# eagle_schematic.net
KiCad netlist of a schematic drawn in EAGLE
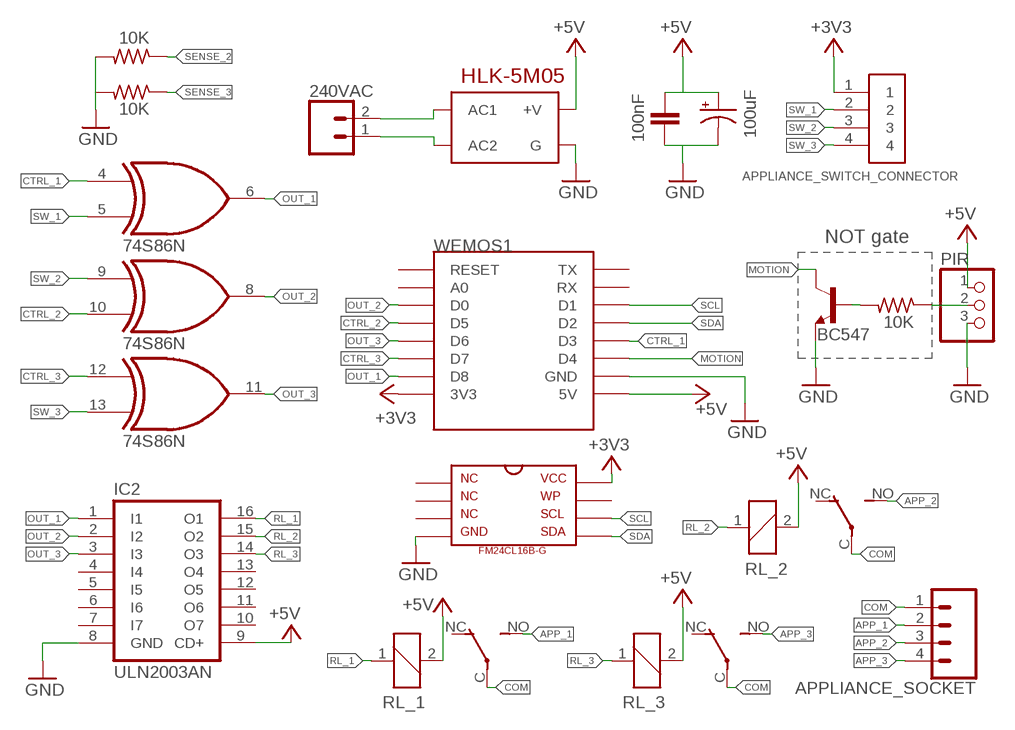
[diagram p0: schematic, sheet 1]

(export (version "E")
  (design (tool "Eeschema 10.0.6"))
  (components
    (comp (ref "240VAC")
      (value "CONN_025MM")
      (footprint "eagle-import:SCREWTERMINAL-5MM-2")
      (libsource (lib "eagle-import") (part "CONN_025MM"))
    )
    (comp (ref "APPLIANCE_SOCKET")
      (value "CONN_04SCREW_LOCK")
      (footprint "eagle-import:SCREWTERMINAL-3.5MM-4_LOCK")
      (libsource (lib "eagle-import") (part "CONN_04SCREW_LOCK"))
    )
    (comp (ref "APPLIANCE_SWITCH_CONNECTOR")
      (value "1X4-BIG")
      (footprint "eagle-import:1X04-BIG")
      (libsource (lib "eagle-import") (part "1X4-BIG"))
    )
    (comp (ref "C1")
      (value "100nF")
      (footprint "eagle-import:C5B2.5")
      (libsource (lib "eagle-import") (part "C5/2.5"))
    )
    (comp (ref "C2")
      (value "100uF")
      (footprint "eagle-import:B45181B")
      (libsource (lib "eagle-import") (part "CPOL-USB45181B"))
    )
    (comp (ref "IC1")
      (value "74S86N")
      (footprint "eagle-import:DIL14")
      (libsource (lib "eagle-import") (part "7486NS"))
    )
    (comp (ref "IC2")
      (value "ULN2003AN")
      (footprint "eagle-import:DIL16")
      (libsource (lib "eagle-import") (part "ULN2003AN"))
    )
    (comp (ref "PIR")
      (value "PINHD-1X3CB")
      (footprint "eagle-import:1X03-CLEANBIG")
      (libsource (lib "eagle-import") (part "PINHD-1X3CB"))
    )
    (comp (ref "R1")
      (value "10K")
      (footprint "eagle-import:0204_7")
      (libsource (lib "eagle-import") (part "R-US_0204/7"))
    )
    (comp (ref "R2")
      (value "10K")
      (footprint "eagle-import:0204_7")
      (libsource (lib "eagle-import") (part "R-US_0204/7"))
    )
    (comp (ref "R3")
      (value "10K")
      (footprint "eagle-import:0204_7")
      (libsource (lib "eagle-import") (part "R-US_0204/7"))
    )
    (comp (ref "RL_1")
      (value "CQ1-12V")
      (footprint "eagle-import:CQ1")
      (libsource (lib "eagle-import") (part "CQ1-12V"))
    )
    (comp (ref "RL_2")
      (value "CQ1-12V")
      (footprint "eagle-import:CQ1")
      (libsource (lib "eagle-import") (part "CQ1-12V"))
    )
    (comp (ref "RL_3")
      (value "CQ1-12V")
      (footprint "eagle-import:CQ1")
      (libsource (lib "eagle-import") (part "CQ1-12V"))
    )
    (comp (ref "T1")
      (value "BC547")
      (footprint "eagle-import:TO92")
      (libsource (lib "eagle-import") (part "BC547"))
    )
    (comp (ref "U$1")
      (value "HLK-5M05")
      (footprint "eagle-import:HLK-5M05")
      (libsource (lib "eagle-import") (part "HLK-5M05"))
    )
    (comp (ref "U$3")
      (value "FM24CL16B-G")
      (footprint "eagle-import:FM24CL16B-G")
      (libsource (lib "eagle-import") (part "FM24CL16B-G"))
    )
    (comp (ref "WEMOS1")
      (value "WEMOS-D1-MINI")
      (footprint "eagle-import:WEMOS-D1-MINI")
      (libsource (lib "eagle-import") (part "WEMOS-D1-MINI"))
    )
  )
  (nets
    (net (code "1") (name "+3V3") (class "Default")
      (node (ref "APPLIANCE_SWITCH_CONNECTOR") (pin "1") (pinfunction "1_1") (pintype "bidirectional"))
      (node (ref "U$3") (pin "8") (pinfunction "8_8") (pintype "power_in"))
      (node (ref "WEMOS1") (pin "3V3") (pinfunction "3V3_3V3") (pintype "bidirectional"))
    )
    (net (code "2") (name "+5V") (class "Default")
      (node (ref "C1") (pin "1") (pinfunction "1_1") (pintype "passive"))
      (node (ref "C2") (pin "+") (pinfunction "+_+") (pintype "passive"))
      (node (ref "IC2") (pin "9") (pinfunction "CD+_9") (pintype "passive"))
      (node (ref "PIR") (pin "1") (pinfunction "1_1") (pintype "passive"))
      (node (ref "RL_1") (pin "2") (pinfunction "2_2") (pintype "passive"))
      (node (ref "RL_2") (pin "2") (pinfunction "2_2") (pintype "passive"))
      (node (ref "RL_3") (pin "2") (pinfunction "2_2") (pintype "passive"))
      (node (ref "U$1") (pin "+V") (pinfunction "+V_+V") (pintype "bidirectional"))
      (node (ref "WEMOS1") (pin "5V") (pinfunction "5V_5V") (pintype "bidirectional"))
    )
    (net (code "3") (name "APP_1") (class "Default")
      (node (ref "APPLIANCE_SOCKET") (pin "2") (pinfunction "2_2") (pintype "passive"))
      (node (ref "RL_1") (pin "NO") (pinfunction "S_NO") (pintype "passive"))
    )
    (net (code "4") (name "APP_2") (class "Default")
      (node (ref "APPLIANCE_SOCKET") (pin "3") (pinfunction "3_3") (pintype "passive"))
      (node (ref "RL_2") (pin "NO") (pinfunction "S_NO") (pintype "passive"))
    )
    (net (code "5") (name "APP_3") (class "Default")
      (node (ref "APPLIANCE_SOCKET") (pin "4") (pinfunction "4_4") (pintype "passive"))
      (node (ref "RL_3") (pin "NO") (pinfunction "S_NO") (pintype "passive"))
    )
    (net (code "6") (name "COM") (class "Default")
      (node (ref "APPLIANCE_SOCKET") (pin "1") (pinfunction "1_1") (pintype "passive"))
      (node (ref "RL_1") (pin "C") (pinfunction "P_C") (pintype "passive"))
      (node (ref "RL_2") (pin "C") (pinfunction "P_C") (pintype "passive"))
      (node (ref "RL_3") (pin "C") (pinfunction "P_C") (pintype "passive"))
    )
    (net (code "7") (name "CTRL_1") (class "Default")
      (node (ref "IC1") (pin "4") (pinfunction "I0_4") (pintype "input"))
      (node (ref "WEMOS1") (pin "D3") (pinfunction "D3_D3") (pintype "bidirectional"))
    )
    (net (code "8") (name "CTRL_2") (class "Default")
      (node (ref "IC1") (pin "10") (pinfunction "I1_10") (pintype "input"))
      (node (ref "WEMOS1") (pin "D5") (pinfunction "D5_D5") (pintype "bidirectional"))
    )
    (net (code "9") (name "CTRL_3") (class "Default")
      (node (ref "IC1") (pin "12") (pinfunction "I0_12") (pintype "input"))
      (node (ref "WEMOS1") (pin "D7") (pinfunction "D7_D7") (pintype "bidirectional"))
    )
    (net (code "10") (name "GND") (class "Default")
      (node (ref "C1") (pin "2") (pinfunction "2_2") (pintype "passive"))
      (node (ref "C2") (pin "-") (pinfunction "-_-") (pintype "passive"))
      (node (ref "IC2") (pin "8") (pinfunction "GND_8") (pintype "power_in"))
      (node (ref "PIR") (pin "3") (pinfunction "3_3") (pintype "passive"))
      (node (ref "R2") (pin "2") (pinfunction "2_2") (pintype "passive"))
      (node (ref "R3") (pin "2") (pinfunction "2_2") (pintype "passive"))
      (node (ref "T1") (pin "1") (pinfunction "E_1") (pintype "passive"))
      (node (ref "U$1") (pin "G") (pinfunction "G_G") (pintype "bidirectional"))
      (node (ref "U$3") (pin "4") (pinfunction "4_4") (pintype "power_in"))
      (node (ref "WEMOS1") (pin "GND") (pinfunction "GND_GND") (pintype "bidirectional"))
    )
    (net (code "11") (name "MOTION") (class "Default")
      (node (ref "T1") (pin "3") (pinfunction "C_3") (pintype "passive"))
      (node (ref "WEMOS1") (pin "D4") (pinfunction "D4_D4") (pintype "bidirectional"))
    )
    (net (code "12") (name "Net-(240VAC-Pad1)") (class "Default")
      (node (ref "240VAC") (pin "1") (pinfunction "1_1") (pintype "passive"))
      (node (ref "U$1") (pin "AC2") (pinfunction "AC2_AC2") (pintype "bidirectional"))
    )
    (net (code "13") (name "Net-(240VAC-Pad2)") (class "Default")
      (node (ref "240VAC") (pin "2") (pinfunction "2_2") (pintype "passive"))
      (node (ref "U$1") (pin "AC1") (pinfunction "AC1_AC1") (pintype "bidirectional"))
    )
    (net (code "14") (name "Net-(PIR-Pad2)") (class "Default")
      (node (ref "PIR") (pin "2") (pinfunction "2_2") (pintype "passive"))
      (node (ref "R1") (pin "1") (pinfunction "1_1") (pintype "passive"))
    )
    (net (code "15") (name "Net-(T1-B)") (class "Default")
      (node (ref "R1") (pin "2") (pinfunction "2_2") (pintype "passive"))
      (node (ref "T1") (pin "2") (pinfunction "B_2") (pintype "passive"))
    )
    (net (code "16") (name "OUT_1") (class "Default")
      (node (ref "IC1") (pin "6") (pinfunction "O_6") (pintype "output"))
      (node (ref "IC2") (pin "1") (pinfunction "I1_1") (pintype "input"))
      (node (ref "WEMOS1") (pin "D8") (pinfunction "D8_D8") (pintype "bidirectional"))
    )
    (net (code "17") (name "OUT_2") (class "Default")
      (node (ref "IC1") (pin "8") (pinfunction "O_8") (pintype "output"))
      (node (ref "IC2") (pin "2") (pinfunction "I2_2") (pintype "input"))
      (node (ref "WEMOS1") (pin "D0") (pinfunction "D0_D0") (pintype "bidirectional"))
    )
    (net (code "18") (name "OUT_3") (class "Default")
      (node (ref "IC1") (pin "11") (pinfunction "O_11") (pintype "output"))
      (node (ref "IC2") (pin "3") (pinfunction "I3_3") (pintype "input"))
      (node (ref "WEMOS1") (pin "D6") (pinfunction "D6_D6") (pintype "bidirectional"))
    )
    (net (code "19") (name "RL_1") (class "Default")
      (node (ref "IC2") (pin "16") (pinfunction "O1_16") (pintype "open_collector"))
      (node (ref "RL_1") (pin "1") (pinfunction "1_1") (pintype "passive"))
    )
    (net (code "20") (name "RL_2") (class "Default")
      (node (ref "IC2") (pin "15") (pinfunction "O2_15") (pintype "open_collector"))
      (node (ref "RL_2") (pin "1") (pinfunction "1_1") (pintype "passive"))
    )
    (net (code "21") (name "RL_3") (class "Default")
      (node (ref "IC2") (pin "14") (pinfunction "O3_14") (pintype "open_collector"))
      (node (ref "RL_3") (pin "1") (pinfunction "1_1") (pintype "passive"))
    )
    (net (code "22") (name "SCL") (class "Default")
      (node (ref "U$3") (pin "6") (pinfunction "6_6") (pintype "input"))
      (node (ref "WEMOS1") (pin "D1") (pinfunction "D1_D1") (pintype "bidirectional"))
    )
    (net (code "23") (name "SDA") (class "Default")
      (node (ref "U$3") (pin "5") (pinfunction "5_5") (pintype "input"))
      (node (ref "WEMOS1") (pin "D2") (pinfunction "D2_D2") (pintype "bidirectional"))
    )
    (net (code "24") (name "SENSE_2") (class "Default")
      (node (ref "R2") (pin "1") (pinfunction "1_1") (pintype "passive"))
    )
    (net (code "25") (name "SENSE_3") (class "Default")
      (node (ref "R3") (pin "1") (pinfunction "1_1") (pintype "passive"))
    )
    (net (code "26") (name "SW_1") (class "Default")
      (node (ref "APPLIANCE_SWITCH_CONNECTOR") (pin "2") (pinfunction "2_2") (pintype "bidirectional"))
      (node (ref "IC1") (pin "5") (pinfunction "I1_5") (pintype "input"))
    )
    (net (code "27") (name "SW_2") (class "Default")
      (node (ref "APPLIANCE_SWITCH_CONNECTOR") (pin "3") (pinfunction "3_3") (pintype "bidirectional"))
      (node (ref "IC1") (pin "9") (pinfunction "I0_9") (pintype "input"))
    )
    (net (code "28") (name "SW_3") (class "Default")
      (node (ref "APPLIANCE_SWITCH_CONNECTOR") (pin "4") (pinfunction "4_4") (pintype "bidirectional"))
      (node (ref "IC1") (pin "13") (pinfunction "I1_13") (pintype "input"))
    )
    (net (code "29") (name "unconnected-(IC2-I4-Pad4)") (class "Default")
      (node (ref "IC2") (pin "4") (pinfunction "I4_4") (pintype "input"))
    )
    (net (code "30") (name "unconnected-(IC2-I5-Pad5)") (class "Default")
      (node (ref "IC2") (pin "5") (pinfunction "I5_5") (pintype "input"))
    )
    (net (code "31") (name "unconnected-(IC2-I6-Pad6)") (class "Default")
      (node (ref "IC2") (pin "6") (pinfunction "I6_6") (pintype "input"))
    )
    (net (code "32") (name "unconnected-(IC2-I7-Pad7)") (class "Default")
      (node (ref "IC2") (pin "7") (pinfunction "I7_7") (pintype "input"))
    )
    (net (code "33") (name "unconnected-(IC2-O4-Pad13)") (class "Default")
      (node (ref "IC2") (pin "13") (pinfunction "O4_13") (pintype "open_collector"))
    )
    (net (code "34") (name "unconnected-(IC2-O5-Pad12)") (class "Default")
      (node (ref "IC2") (pin "12") (pinfunction "O5_12") (pintype "open_collector"))
    )
    (net (code "35") (name "unconnected-(IC2-O6-Pad11)") (class "Default")
      (node (ref "IC2") (pin "11") (pinfunction "O6_11") (pintype "open_collector"))
    )
    (net (code "36") (name "unconnected-(IC2-O7-Pad10)") (class "Default")
      (node (ref "IC2") (pin "10") (pinfunction "O7_10") (pintype "open_collector"))
    )
    (net (code "37") (name "unconnected-(RL_1B-O-PadNC)") (class "Default")
      (node (ref "RL_1") (pin "NC") (pinfunction "O_NC") (pintype "passive"))
    )
    (net (code "38") (name "unconnected-(RL_2B-O-PadNC)") (class "Default")
      (node (ref "RL_2") (pin "NC") (pinfunction "O_NC") (pintype "passive"))
    )
    (net (code "39") (name "unconnected-(RL_3B-O-PadNC)") (class "Default")
      (node (ref "RL_3") (pin "NC") (pinfunction "O_NC") (pintype "passive"))
    )
    (net (code "40") (name "unconnected-(U$3-Pad1)") (class "Default")
      (node (ref "U$3") (pin "1") (pinfunction "1_1") (pintype "no_connect"))
    )
    (net (code "41") (name "unconnected-(U$3-Pad2)") (class "Default")
      (node (ref "U$3") (pin "2") (pinfunction "2_2") (pintype "no_connect"))
    )
    (net (code "42") (name "unconnected-(U$3-Pad3)") (class "Default")
      (node (ref "U$3") (pin "3") (pinfunction "3_3") (pintype "no_connect"))
    )
    (net (code "43") (name "unconnected-(U$3-Pad7)") (class "Default")
      (node (ref "U$3") (pin "7") (pinfunction "7_7") (pintype "bidirectional"))
    )
    (net (code "44") (name "unconnected-(WEMOS1-PadA0)") (class "Default")
      (node (ref "WEMOS1") (pin "A0") (pinfunction "A0_A0") (pintype "bidirectional"))
    )
    (net (code "45") (name "unconnected-(WEMOS1-PadRESET)") (class "Default")
      (node (ref "WEMOS1") (pin "RESET") (pinfunction "RESET_RESET") (pintype "bidirectional"))
    )
    (net (code "46") (name "unconnected-(WEMOS1-PadRX)") (class "Default")
      (node (ref "WEMOS1") (pin "RX") (pinfunction "RX_RX") (pintype "bidirectional"))
    )
    (net (code "47") (name "unconnected-(WEMOS1-PadTX)") (class "Default")
      (node (ref "WEMOS1") (pin "TX") (pinfunction "TX_TX") (pintype "bidirectional"))
    )
  )
)
